# isolation.net
KiCad netlist of a schematic drawn in Altium Designer
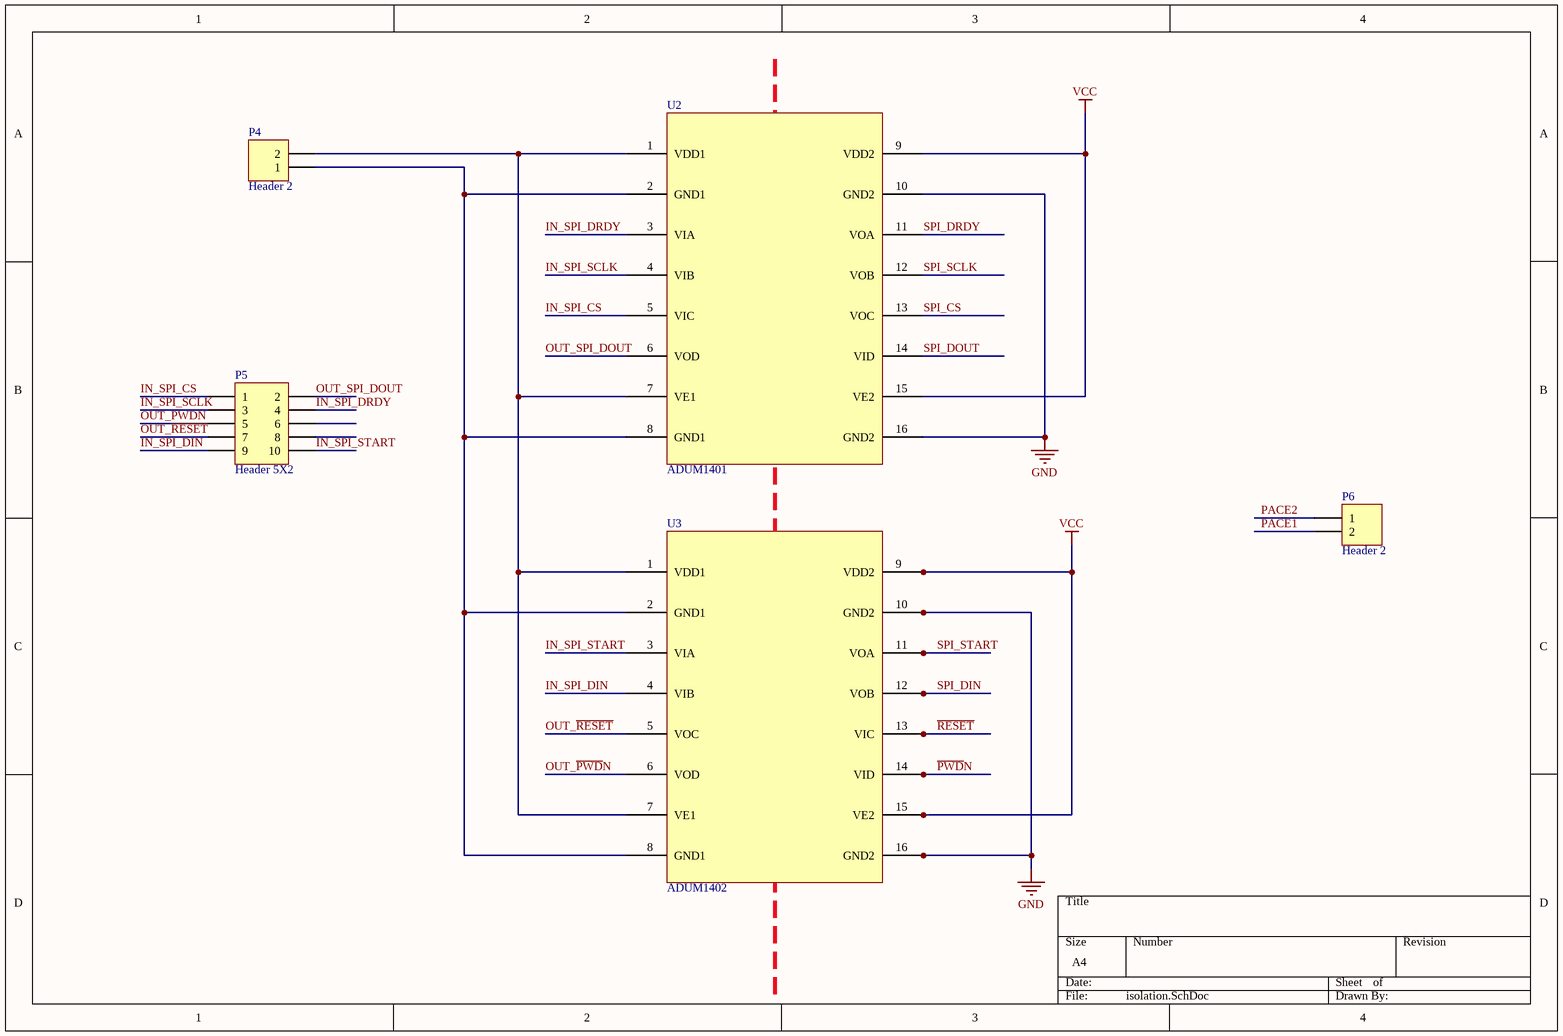
[diagram p0: isolation.SchDoc]

(export (version "E")
  (design (tool "Eeschema 10.0.6"))
  (components
    (comp (ref "P4")
      (value "Header 2")
      (footprint "HDR1X2")
      (description "Header, 2-Pin")
      (fields (field (name "PUBLISHER") "Altium Limited"))
      (libsource (lib "") (part "Header 2_1"))
    )
    (comp (ref "P5")
      (value "Header 5X2")
      (footprint "HDR2X5")
      (description "Header, 5-Pin, Dual row")
      (fields (field (name "PUBLISHER") "Altium Limited"))
      (libsource (lib "Miscellaneous Connectors") (part "Header 5X2"))
    )
    (comp (ref "P6")
      (value "Header 2")
      (footprint "HDR1X2")
      (description "Header, 2-Pin")
      (fields (field (name "PUBLISHER") "Altium Limited"))
      (libsource (lib "Miscellaneous Connectors") (part "Header 2"))
    )
    (comp (ref "U2")
      (value "ADUM1401")
      (footprint "SOIC_W")
      (description "ADI isolation")
      (libsource (lib "walkeeg_lib") (part "ADUM1401"))
    )
    (comp (ref "U3")
      (value "ADUM1402")
      (footprint "SOIC_W")
      (libsource (lib "walkeeg_lib") (part "ADUM1402"))
    )
  )
  (nets
    (net (code "1") (name "/IN_SPI_CS") (class "Default")
      (node (ref "P5") (pin "1") (pinfunction "1_1") (pintype "passive"))
      (node (ref "U2") (pin "5") (pinfunction "VIC_5") (pintype "passive"))
    )
    (net (code "2") (name "/IN_SPI_DIN") (class "Default")
      (node (ref "P5") (pin "9") (pinfunction "9_9") (pintype "passive"))
      (node (ref "U3") (pin "4") (pinfunction "VIB_4") (pintype "passive"))
    )
    (net (code "3") (name "/IN_SPI_DRDY") (class "Default")
      (node (ref "P5") (pin "4") (pinfunction "4_4") (pintype "passive"))
      (node (ref "U2") (pin "3") (pinfunction "VIA_3") (pintype "passive"))
    )
    (net (code "4") (name "/IN_SPI_SCLK") (class "Default")
      (node (ref "P5") (pin "3") (pinfunction "3_3") (pintype "passive"))
      (node (ref "U2") (pin "4") (pinfunction "VIB_4") (pintype "passive"))
    )
    (net (code "5") (name "/IN_SPI_START") (class "Default")
      (node (ref "P5") (pin "10") (pinfunction "10_10") (pintype "passive"))
      (node (ref "U3") (pin "3") (pinfunction "VIA_3") (pintype "passive"))
    )
    (net (code "6") (name "/OUT_SPI_DOUT") (class "Default")
      (node (ref "P5") (pin "2") (pinfunction "2_2") (pintype "passive"))
      (node (ref "U2") (pin "6") (pinfunction "VOD_6") (pintype "passive"))
    )
    (net (code "7") (name "/OUT_~{PWD}N") (class "Default")
      (node (ref "P5") (pin "5") (pinfunction "5_5") (pintype "passive"))
      (node (ref "U3") (pin "6") (pinfunction "VOD_6") (pintype "passive"))
    )
    (net (code "8") (name "/OUT_~{RESET}") (class "Default")
      (node (ref "P5") (pin "7") (pinfunction "7_7") (pintype "passive"))
      (node (ref "U3") (pin "5") (pinfunction "VOC_5") (pintype "passive"))
    )
    (net (code "9") (name "/PACE1") (class "Default")
      (node (ref "P6") (pin "2") (pinfunction "2_2") (pintype "passive"))
    )
    (net (code "10") (name "/PACE2") (class "Default")
      (node (ref "P6") (pin "1") (pinfunction "1_1") (pintype "passive"))
    )
    (net (code "11") (name "/SPI_CS") (class "Default")
      (node (ref "U2") (pin "13") (pinfunction "VOC_13") (pintype "passive"))
    )
    (net (code "12") (name "/SPI_DIN") (class "Default")
      (node (ref "U3") (pin "12") (pinfunction "VOB_12") (pintype "passive"))
    )
    (net (code "13") (name "/SPI_DOUT") (class "Default")
      (node (ref "U2") (pin "14") (pinfunction "VID_14") (pintype "passive"))
    )
    (net (code "14") (name "/SPI_DRDY") (class "Default")
      (node (ref "U2") (pin "11") (pinfunction "VOA_11") (pintype "passive"))
    )
    (net (code "15") (name "/SPI_SCLK") (class "Default")
      (node (ref "U2") (pin "12") (pinfunction "VOB_12") (pintype "passive"))
    )
    (net (code "16") (name "/SPI_START") (class "Default")
      (node (ref "U3") (pin "11") (pinfunction "VOA_11") (pintype "passive"))
    )
    (net (code "17") (name "/~{PWD}N") (class "Default")
      (node (ref "U3") (pin "14") (pinfunction "VID_14") (pintype "passive"))
    )
    (net (code "18") (name "/~{RESET}") (class "Default")
      (node (ref "U3") (pin "13") (pinfunction "VIC_13") (pintype "passive"))
    )
    (net (code "19") (name "GND") (class "Default")
      (node (ref "U2") (pin "10") (pinfunction "GND2_10") (pintype "passive"))
      (node (ref "U2") (pin "16") (pinfunction "GND2_16") (pintype "passive"))
      (node (ref "U3") (pin "10") (pinfunction "GND2_10") (pintype "passive"))
      (node (ref "U3") (pin "16") (pinfunction "GND2_16") (pintype "passive"))
    )
    (net (code "20") (name "Net-(P4-Pad1)") (class "Default")
      (node (ref "P4") (pin "1") (pinfunction "1_1") (pintype "passive"))
      (node (ref "U2") (pin "2") (pinfunction "GND1_2") (pintype "passive"))
      (node (ref "U2") (pin "8") (pinfunction "GND1_8") (pintype "passive"))
      (node (ref "U3") (pin "2") (pinfunction "GND1_2") (pintype "passive"))
      (node (ref "U3") (pin "8") (pinfunction "GND1_8") (pintype "passive"))
    )
    (net (code "21") (name "Net-(U2-VDD1)") (class "Default")
      (node (ref "P4") (pin "2") (pinfunction "2_2") (pintype "passive"))
      (node (ref "U2") (pin "1") (pinfunction "VDD1_1") (pintype "passive"))
      (node (ref "U2") (pin "7") (pinfunction "VE1_7") (pintype "passive"))
      (node (ref "U3") (pin "1") (pinfunction "VDD1_1") (pintype "passive"))
      (node (ref "U3") (pin "7") (pinfunction "VE1_7") (pintype "passive"))
    )
    (net (code "22") (name "VCC") (class "Default")
      (node (ref "U2") (pin "15") (pinfunction "VE2_15") (pintype "passive"))
      (node (ref "U2") (pin "9") (pinfunction "VDD2_9") (pintype "passive"))
      (node (ref "U3") (pin "15") (pinfunction "VE2_15") (pintype "passive"))
      (node (ref "U3") (pin "9") (pinfunction "VDD2_9") (pintype "passive"))
    )
    (net (code "23") (name "unconnected-(P5-Pad6)") (class "Default")
      (node (ref "P5") (pin "6") (pinfunction "6_6") (pintype "passive"))
    )
    (net (code "24") (name "unconnected-(P5-Pad8)") (class "Default")
      (node (ref "P5") (pin "8") (pinfunction "8_8") (pintype "passive"))
    )
  )
)
